# Inputs_Fast.net
KiCad netlist of a schematic drawn in Altium Designer
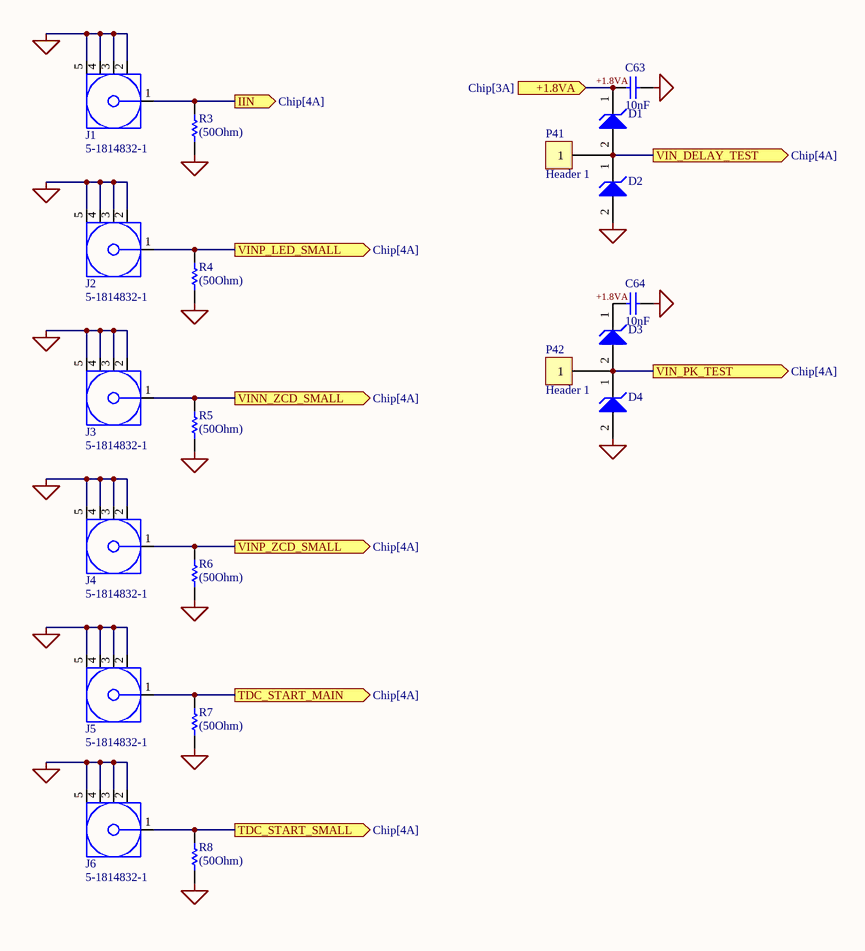
[diagram p0: Inputs_Fast.SchDoc]

(export (version "E")
  (design (tool "Eeschema 10.0.6"))
  (components
    (comp (ref "C63")
      (value "10nF")
      (footprint "CAPC1608X90X35ML10T15")
      (description "0603")
      (fields (field (name "MANUFACTURER") "Murata"))
      (libsource (lib "Altium Content Vault") (part "CAP-NP-2"))
    )
    (comp (ref "C64")
      (value "10nF")
      (footprint "CAPC1608X90X35ML10T15")
      (description "0603")
      (fields (field (name "MANUFACTURER") "Murata"))
      (libsource (lib "Altium Content Vault") (part "CAP-NP-2"))
    )
    (comp (ref "D1")
      (value "~")
      (footprint "ONSC-SOD-123-2-425-04_V")
      (description "Zener Voltage Regulator, 2-Pin SOD-123, Pb-Free, Tape and Reel")
      (fields (field (name "MANUFACTURER") "On Semiconductor") (field (name "PARTNUMBER") "MMSZ4679T1G"))
      (libsource (lib "Altium Content Vault") (part "ONSC-K1A2-2"))
    )
    (comp (ref "D2")
      (value "~")
      (footprint "ONSC-SOD-123-2-425-04_V")
      (description "Zener Voltage Regulator, 2-Pin SOD-123, Pb-Free, Tape and Reel")
      (fields (field (name "MANUFACTURER") "On Semiconductor") (field (name "PARTNUMBER") "MMSZ4679T1G"))
      (libsource (lib "Altium Content Vault") (part "ONSC-K1A2-2"))
    )
    (comp (ref "D3")
      (value "~")
      (footprint "ONSC-SOD-123-2-425-04_V")
      (description "Zener Voltage Regulator, 2-Pin SOD-123, Pb-Free, Tape and Reel")
      (fields (field (name "MANUFACTURER") "On Semiconductor") (field (name "PARTNUMBER") "MMSZ4679T1G"))
      (libsource (lib "Altium Content Vault") (part "ONSC-K1A2-2"))
    )
    (comp (ref "D4")
      (value "~")
      (footprint "ONSC-SOD-123-2-425-04_V")
      (description "Zener Voltage Regulator, 2-Pin SOD-123, Pb-Free, Tape and Reel")
      (fields (field (name "MANUFACTURER") "On Semiconductor") (field (name "PARTNUMBER") "MMSZ4679T1G"))
      (libsource (lib "Altium Content Vault") (part "ONSC-K1A2-2"))
    )
    (comp (ref "J1")
      (value "5-1814832-1")
      (footprint "TECO-5-1814832-1_V")
      (fields (field (name "MANUFACTURER") "TE Connectivity"))
      (libsource (lib "Altium Content Vault") (part "CN-S-4F-RF5"))
    )
    (comp (ref "J2")
      (value "5-1814832-1")
      (footprint "TECO-5-1814832-1_V")
      (fields (field (name "MANUFACTURER") "TE Connectivity"))
      (libsource (lib "Altium Content Vault") (part "CN-S-4F-RF5"))
    )
    (comp (ref "J3")
      (value "5-1814832-1")
      (footprint "TECO-5-1814832-1_V")
      (fields (field (name "MANUFACTURER") "TE Connectivity"))
      (libsource (lib "Altium Content Vault") (part "CN-S-4F-RF5"))
    )
    (comp (ref "J4")
      (value "5-1814832-1")
      (footprint "TECO-5-1814832-1_V")
      (fields (field (name "MANUFACTURER") "TE Connectivity"))
      (libsource (lib "Altium Content Vault") (part "CN-S-4F-RF5"))
    )
    (comp (ref "J5")
      (value "5-1814832-1")
      (footprint "TECO-5-1814832-1_V")
      (fields (field (name "MANUFACTURER") "TE Connectivity"))
      (libsource (lib "Altium Content Vault") (part "CN-S-4F-RF5"))
    )
    (comp (ref "J6")
      (value "5-1814832-1")
      (footprint "TECO-5-1814832-1_V")
      (fields (field (name "MANUFACTURER") "TE Connectivity"))
      (libsource (lib "Altium Content Vault") (part "CN-S-4F-RF5"))
    )
    (comp (ref "P41") (value "Header 1") (footprint "Header1") (libsource (lib "intlib") (part "Header 1")))
    (comp (ref "P42") (value "Header 1") (footprint "Header1") (libsource (lib "intlib") (part "Header 1")))
    (comp (ref "R3")
      (value "(50Ohm)")
      (footprint "RESC1609X50X30NL8T20")
      (description "0603")
      (fields (field (name "MANUFACTURER") "Vishay Semiconductor"))
      (libsource (lib "Altium Content Vault") (part "RES-2"))
    )
    (comp (ref "R4")
      (value "(50Ohm)")
      (footprint "RESC1609X50X30NL8T20")
      (description "0603")
      (fields (field (name "MANUFACTURER") "Vishay Semiconductor"))
      (libsource (lib "Altium Content Vault") (part "RES-2"))
    )
    (comp (ref "R5")
      (value "(50Ohm)")
      (footprint "RESC1609X50X30NL8T20")
      (description "0603")
      (fields (field (name "MANUFACTURER") "Vishay Semiconductor"))
      (libsource (lib "Altium Content Vault") (part "RES-2"))
    )
    (comp (ref "R6")
      (value "(50Ohm)")
      (footprint "RESC1609X50X30NL8T20")
      (description "0603")
      (fields (field (name "MANUFACTURER") "Vishay Semiconductor"))
      (libsource (lib "Altium Content Vault") (part "RES-2"))
    )
    (comp (ref "R7")
      (value "(50Ohm)")
      (footprint "RESC1609X50X30NL8T20")
      (description "0603")
      (fields (field (name "MANUFACTURER") "Vishay Semiconductor"))
      (libsource (lib "Altium Content Vault") (part "RES-2"))
    )
    (comp (ref "R8")
      (value "(50Ohm)")
      (footprint "RESC1609X50X30NL8T20")
      (description "0603")
      (fields (field (name "MANUFACTURER") "Vishay Semiconductor"))
      (libsource (lib "Altium Content Vault") (part "RES-2"))
    )
  )
  (nets
    (net (code "1") (name "/+1.8VA") (class "Default")
      (node (ref "C63") (pin "2") (pinfunction "2_2") (pintype "passive"))
      (node (ref "C64") (pin "2") (pinfunction "2_2") (pintype "passive"))
      (node (ref "D1") (pin "1") (pinfunction "K_1") (pintype "passive"))
      (node (ref "D3") (pin "1") (pinfunction "K_1") (pintype "passive"))
    )
    (net (code "2") (name "/IIN") (class "Default")
      (node (ref "J1") (pin "1") (pinfunction "1_1") (pintype "passive"))
      (node (ref "R3") (pin "2") (pinfunction "2_2") (pintype "passive"))
    )
    (net (code "3") (name "/TDC_START_MAIN") (class "Default")
      (node (ref "J5") (pin "1") (pinfunction "1_1") (pintype "passive"))
      (node (ref "R7") (pin "2") (pinfunction "2_2") (pintype "passive"))
    )
    (net (code "4") (name "/TDC_START_SMALL") (class "Default")
      (node (ref "J6") (pin "1") (pinfunction "1_1") (pintype "passive"))
      (node (ref "R8") (pin "2") (pinfunction "2_2") (pintype "passive"))
    )
    (net (code "5") (name "/VINN_ZCD_SMALL") (class "Default")
      (node (ref "J3") (pin "1") (pinfunction "1_1") (pintype "passive"))
      (node (ref "R5") (pin "2") (pinfunction "2_2") (pintype "passive"))
    )
    (net (code "6") (name "/VINP_LED_SMALL") (class "Default")
      (node (ref "J2") (pin "1") (pinfunction "1_1") (pintype "passive"))
      (node (ref "R4") (pin "2") (pinfunction "2_2") (pintype "passive"))
    )
    (net (code "7") (name "/VINP_ZCD_SMALL") (class "Default")
      (node (ref "J4") (pin "1") (pinfunction "1_1") (pintype "passive"))
      (node (ref "R6") (pin "2") (pinfunction "2_2") (pintype "passive"))
    )
    (net (code "8") (name "/VIN_DELAY_TEST") (class "Default")
      (node (ref "D1") (pin "2") (pinfunction "A_2") (pintype "passive"))
      (node (ref "D2") (pin "1") (pinfunction "K_1") (pintype "passive"))
      (node (ref "P41") (pin "1") (pinfunction "1_1") (pintype "passive"))
    )
    (net (code "9") (name "/VIN_PK_TEST") (class "Default")
      (node (ref "D3") (pin "2") (pinfunction "A_2") (pintype "passive"))
      (node (ref "D4") (pin "1") (pinfunction "K_1") (pintype "passive"))
      (node (ref "P42") (pin "1") (pinfunction "1_1") (pintype "passive"))
    )
    (net (code "10") (name "GND") (class "Default")
      (node (ref "C63") (pin "1") (pinfunction "1_1") (pintype "passive"))
      (node (ref "C64") (pin "1") (pinfunction "1_1") (pintype "passive"))
      (node (ref "D2") (pin "2") (pinfunction "A_2") (pintype "passive"))
      (node (ref "D4") (pin "2") (pinfunction "A_2") (pintype "passive"))
      (node (ref "J1") (pin "2") (pinfunction "2_2") (pintype "passive"))
      (node (ref "J1") (pin "3") (pinfunction "3_3") (pintype "passive"))
      (node (ref "J1") (pin "4") (pinfunction "4_4") (pintype "passive"))
      (node (ref "J1") (pin "5") (pinfunction "5_5") (pintype "passive"))
      (node (ref "J2") (pin "2") (pinfunction "2_2") (pintype "passive"))
      (node (ref "J2") (pin "3") (pinfunction "3_3") (pintype "passive"))
      (node (ref "J2") (pin "4") (pinfunction "4_4") (pintype "passive"))
      (node (ref "J2") (pin "5") (pinfunction "5_5") (pintype "passive"))
      (node (ref "J3") (pin "2") (pinfunction "2_2") (pintype "passive"))
      (node (ref "J3") (pin "3") (pinfunction "3_3") (pintype "passive"))
      (node (ref "J3") (pin "4") (pinfunction "4_4") (pintype "passive"))
      (node (ref "J3") (pin "5") (pinfunction "5_5") (pintype "passive"))
      (node (ref "J4") (pin "2") (pinfunction "2_2") (pintype "passive"))
      (node (ref "J4") (pin "3") (pinfunction "3_3") (pintype "passive"))
      (node (ref "J4") (pin "4") (pinfunction "4_4") (pintype "passive"))
      (node (ref "J4") (pin "5") (pinfunction "5_5") (pintype "passive"))
      (node (ref "J5") (pin "2") (pinfunction "2_2") (pintype "passive"))
      (node (ref "J5") (pin "3") (pinfunction "3_3") (pintype "passive"))
      (node (ref "J5") (pin "4") (pinfunction "4_4") (pintype "passive"))
      (node (ref "J5") (pin "5") (pinfunction "5_5") (pintype "passive"))
      (node (ref "J6") (pin "2") (pinfunction "2_2") (pintype "passive"))
      (node (ref "J6") (pin "3") (pinfunction "3_3") (pintype "passive"))
      (node (ref "J6") (pin "4") (pinfunction "4_4") (pintype "passive"))
      (node (ref "J6") (pin "5") (pinfunction "5_5") (pintype "passive"))
      (node (ref "R3") (pin "1") (pinfunction "1_1") (pintype "passive"))
      (node (ref "R4") (pin "1") (pinfunction "1_1") (pintype "passive"))
      (node (ref "R5") (pin "1") (pinfunction "1_1") (pintype "passive"))
      (node (ref "R6") (pin "1") (pinfunction "1_1") (pintype "passive"))
      (node (ref "R7") (pin "1") (pinfunction "1_1") (pintype "passive"))
      (node (ref "R8") (pin "1") (pinfunction "1_1") (pintype "passive"))
    )
  )
)
